# Nixie_Control_Board.net
KiCad netlist of a schematic drawn in EasyEDA
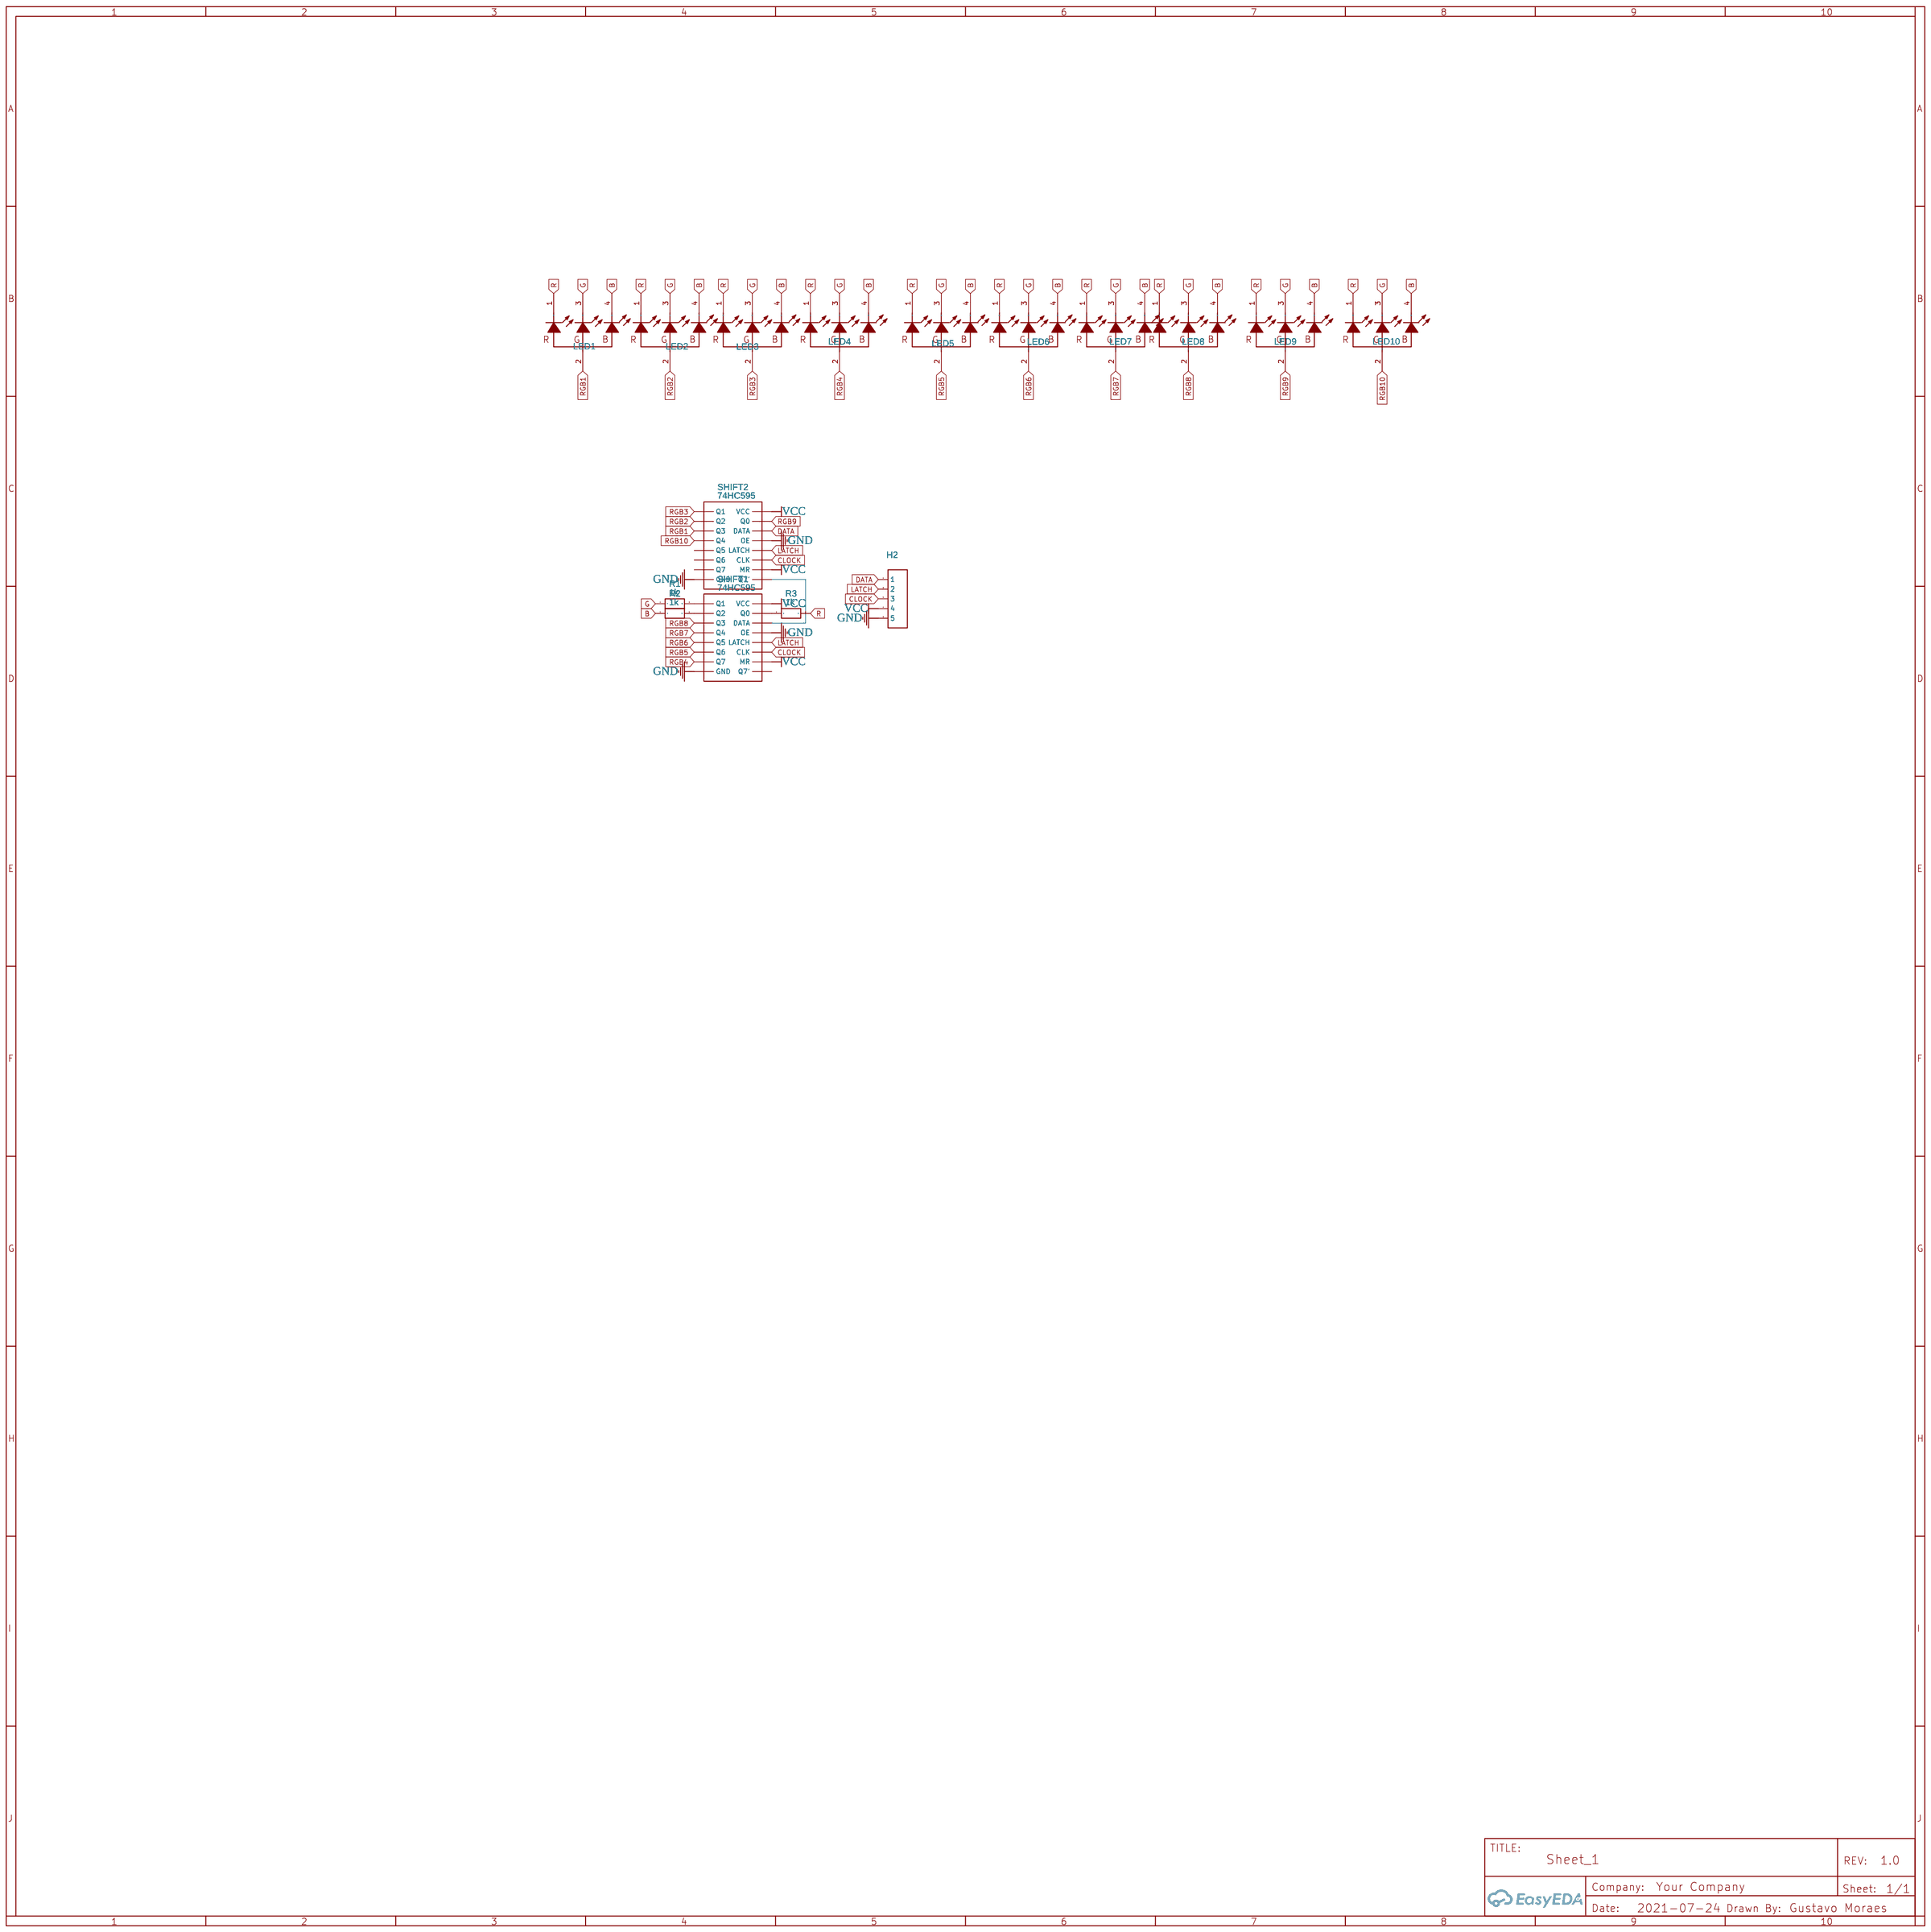
[diagram p0: schematic sheet]

(export (version "E")
  (design (tool "Eeschema 10.0.6"))
  (components
    (comp (ref "H2")
      (value "HDR-F-2.54_1x5")
      (fields (field (name "BOM_Supplier Part") "C50950"))
      (libsource (lib "") (part "HDR-F-2.54_1x5"))
    )
    (comp (ref "LED1")
      (value "φ5 RGB Transparent")
      (fields
        (field (name "BOM_Manufacturer Part") "φ5 RGB Transparent LED")
        (field (name "BOM_Supplier Part") "C32985")
      )
      (libsource (lib "") (part "φ5 RGB Transparent"))
    )
    (comp (ref "LED2")
      (value "φ5 RGB Transparent")
      (fields
        (field (name "BOM_Manufacturer Part") "φ5 RGB Transparent LED")
        (field (name "BOM_Supplier Part") "C32985")
      )
      (libsource (lib "") (part "φ5 RGB Transparent"))
    )
    (comp (ref "LED3")
      (value "φ5 RGB Transparent")
      (fields
        (field (name "BOM_Manufacturer Part") "φ5 RGB Transparent LED")
        (field (name "BOM_Supplier Part") "C32985")
      )
      (libsource (lib "") (part "φ5 RGB Transparent"))
    )
    (comp (ref "LED4")
      (value "φ5 RGB Transparent")
      (fields
        (field (name "BOM_Manufacturer Part") "φ5 RGB Transparent LED")
        (field (name "BOM_Supplier Part") "C32985")
      )
      (libsource (lib "") (part "φ5 RGB Transparent_1"))
    )
    (comp (ref "LED5")
      (value "φ5 RGB Transparent")
      (fields
        (field (name "BOM_Manufacturer Part") "φ5 RGB Transparent LED")
        (field (name "BOM_Supplier Part") "C32985")
      )
      (libsource (lib "") (part "φ5 RGB Transparent"))
    )
    (comp (ref "LED6")
      (value "φ5 RGB Transparent")
      (fields
        (field (name "BOM_Manufacturer Part") "φ5 RGB Transparent LED")
        (field (name "BOM_Supplier Part") "C32985")
      )
      (libsource (lib "") (part "φ5 RGB Transparent"))
    )
    (comp (ref "LED7")
      (value "φ5 RGB Transparent")
      (fields
        (field (name "BOM_Manufacturer Part") "φ5 RGB Transparent LED")
        (field (name "BOM_Supplier Part") "C32985")
      )
      (libsource (lib "") (part "φ5 RGB Transparent"))
    )
    (comp (ref "LED8")
      (value "φ5 RGB Transparent")
      (fields
        (field (name "BOM_Manufacturer Part") "φ5 RGB Transparent LED")
        (field (name "BOM_Supplier Part") "C32985")
      )
      (libsource (lib "") (part "φ5 RGB Transparent"))
    )
    (comp (ref "LED9")
      (value "φ5 RGB Transparent")
      (fields
        (field (name "BOM_Manufacturer Part") "φ5 RGB Transparent LED")
        (field (name "BOM_Supplier Part") "C32985")
      )
      (libsource (lib "") (part "φ5 RGB Transparent"))
    )
    (comp (ref "LED10")
      (value "φ5 RGB Transparent")
      (fields
        (field (name "BOM_Manufacturer Part") "φ5 RGB Transparent LED")
        (field (name "BOM_Supplier Part") "C32985")
      )
      (libsource (lib "") (part "φ5 RGB Transparent"))
    )
    (comp (ref "R1") (value "1k") (libsource (lib "") (part "R_AXIAL-0.3_EU")))
    (comp (ref "R2") (value "1k") (libsource (lib "") (part "R_AXIAL-0.3_EU")))
    (comp (ref "R3") (value "1k") (libsource (lib "") (part "R_AXIAL-0.3_EU")))
    (comp (ref "SHIFT1") (value "74HC595") (libsource (lib "") (part "74HC595")))
    (comp (ref "SHIFT2") (value "74HC595") (libsource (lib "") (part "74HC595")))
  )
  (nets
    (net (code "1") (name "B") (class "Default")
      (node (ref "LED1") (pin "4") (pinfunction "KB_4") (pintype "unspecified"))
      (node (ref "LED10") (pin "4") (pinfunction "KB_4") (pintype "unspecified"))
      (node (ref "LED2") (pin "4") (pinfunction "KB_4") (pintype "unspecified"))
      (node (ref "LED3") (pin "4") (pinfunction "KB_4") (pintype "unspecified"))
      (node (ref "LED4") (pin "4") (pinfunction "KB_4") (pintype "unspecified"))
      (node (ref "LED5") (pin "4") (pinfunction "KB_4") (pintype "unspecified"))
      (node (ref "LED6") (pin "4") (pinfunction "KB_4") (pintype "unspecified"))
      (node (ref "LED7") (pin "4") (pinfunction "KB_4") (pintype "unspecified"))
      (node (ref "LED8") (pin "4") (pinfunction "KB_4") (pintype "unspecified"))
      (node (ref "LED9") (pin "4") (pinfunction "KB_4") (pintype "unspecified"))
      (node (ref "R2") (pin "1") (pinfunction "1_1") (pintype "unspecified"))
    )
    (net (code "2") (name "CLOCK") (class "Default")
      (node (ref "H2") (pin "3") (pinfunction "3_3") (pintype "unspecified"))
      (node (ref "SHIFT1") (pin "11") (pinfunction "CLK_11") (pintype "unspecified"))
      (node (ref "SHIFT2") (pin "11") (pinfunction "CLK_11") (pintype "unspecified"))
    )
    (net (code "3") (name "DATA") (class "Default")
      (node (ref "H2") (pin "1") (pinfunction "1_1") (pintype "unspecified"))
      (node (ref "SHIFT2") (pin "14") (pinfunction "DATA_14") (pintype "unspecified"))
    )
    (net (code "4") (name "G") (class "Default")
      (node (ref "LED1") (pin "3") (pinfunction "KG_3") (pintype "unspecified"))
      (node (ref "LED10") (pin "3") (pinfunction "KG_3") (pintype "unspecified"))
      (node (ref "LED2") (pin "3") (pinfunction "KG_3") (pintype "unspecified"))
      (node (ref "LED3") (pin "3") (pinfunction "KG_3") (pintype "unspecified"))
      (node (ref "LED4") (pin "3") (pinfunction "KG_3") (pintype "unspecified"))
      (node (ref "LED5") (pin "3") (pinfunction "KG_3") (pintype "unspecified"))
      (node (ref "LED6") (pin "3") (pinfunction "KG_3") (pintype "unspecified"))
      (node (ref "LED7") (pin "3") (pinfunction "KG_3") (pintype "unspecified"))
      (node (ref "LED8") (pin "3") (pinfunction "KG_3") (pintype "unspecified"))
      (node (ref "LED9") (pin "3") (pinfunction "KG_3") (pintype "unspecified"))
      (node (ref "R1") (pin "1") (pinfunction "1_1") (pintype "unspecified"))
    )
    (net (code "5") (name "GND") (class "Default")
      (node (ref "H2") (pin "5") (pinfunction "5_5") (pintype "unspecified"))
      (node (ref "SHIFT1") (pin "13") (pinfunction "OE_13") (pintype "unspecified"))
      (node (ref "SHIFT1") (pin "8") (pinfunction "GND_8") (pintype "unspecified"))
      (node (ref "SHIFT2") (pin "13") (pinfunction "OE_13") (pintype "unspecified"))
      (node (ref "SHIFT2") (pin "8") (pinfunction "GND_8") (pintype "unspecified"))
    )
    (net (code "6") (name "LATCH") (class "Default")
      (node (ref "H2") (pin "2") (pinfunction "2_2") (pintype "unspecified"))
      (node (ref "SHIFT1") (pin "12") (pinfunction "LATCH_12") (pintype "unspecified"))
      (node (ref "SHIFT2") (pin "12") (pinfunction "LATCH_12") (pintype "unspecified"))
    )
    (net (code "7") (name "Net-(SHIFT1-DATA)") (class "Default")
      (node (ref "SHIFT1") (pin "14") (pinfunction "DATA_14") (pintype "unspecified"))
      (node (ref "SHIFT2") (pin "9") (pinfunction "Q7'_9") (pintype "unspecified"))
    )
    (net (code "8") (name "Net-(SHIFT1-Q0)") (class "Default")
      (node (ref "R3") (pin "1") (pinfunction "1_1") (pintype "unspecified"))
      (node (ref "SHIFT1") (pin "15") (pinfunction "Q0_15") (pintype "unspecified"))
    )
    (net (code "9") (name "Net-(SHIFT1-Q1)") (class "Default")
      (node (ref "R1") (pin "2") (pinfunction "2_2") (pintype "unspecified"))
      (node (ref "SHIFT1") (pin "1") (pinfunction "Q1_1") (pintype "unspecified"))
    )
    (net (code "10") (name "Net-(SHIFT1-Q2)") (class "Default")
      (node (ref "R2") (pin "2") (pinfunction "2_2") (pintype "unspecified"))
      (node (ref "SHIFT1") (pin "2") (pinfunction "Q2_2") (pintype "unspecified"))
    )
    (net (code "11") (name "R") (class "Default")
      (node (ref "LED1") (pin "1") (pinfunction "KR_1") (pintype "unspecified"))
      (node (ref "LED10") (pin "1") (pinfunction "KR_1") (pintype "unspecified"))
      (node (ref "LED2") (pin "1") (pinfunction "KR_1") (pintype "unspecified"))
      (node (ref "LED3") (pin "1") (pinfunction "KR_1") (pintype "unspecified"))
      (node (ref "LED4") (pin "1") (pinfunction "KR_1") (pintype "unspecified"))
      (node (ref "LED5") (pin "1") (pinfunction "KR_1") (pintype "unspecified"))
      (node (ref "LED6") (pin "1") (pinfunction "KR_1") (pintype "unspecified"))
      (node (ref "LED7") (pin "1") (pinfunction "KR_1") (pintype "unspecified"))
      (node (ref "LED8") (pin "1") (pinfunction "KR_1") (pintype "unspecified"))
      (node (ref "LED9") (pin "1") (pinfunction "KR_1") (pintype "unspecified"))
      (node (ref "R3") (pin "2") (pinfunction "2_2") (pintype "unspecified"))
    )
    (net (code "12") (name "RGB1") (class "Default")
      (node (ref "LED1") (pin "2") (pinfunction "CA_2") (pintype "unspecified"))
      (node (ref "SHIFT2") (pin "3") (pinfunction "Q3_3") (pintype "unspecified"))
    )
    (net (code "13") (name "RGB2") (class "Default")
      (node (ref "LED2") (pin "2") (pinfunction "CA_2") (pintype "unspecified"))
      (node (ref "SHIFT2") (pin "2") (pinfunction "Q2_2") (pintype "unspecified"))
    )
    (net (code "14") (name "RGB3") (class "Default")
      (node (ref "LED3") (pin "2") (pinfunction "CA_2") (pintype "unspecified"))
      (node (ref "SHIFT2") (pin "1") (pinfunction "Q1_1") (pintype "unspecified"))
    )
    (net (code "15") (name "RGB4") (class "Default")
      (node (ref "LED4") (pin "2") (pinfunction "CA_2") (pintype "unspecified"))
      (node (ref "SHIFT1") (pin "7") (pinfunction "Q7_7") (pintype "unspecified"))
    )
    (net (code "16") (name "RGB5") (class "Default")
      (node (ref "LED5") (pin "2") (pinfunction "CA_2") (pintype "unspecified"))
      (node (ref "SHIFT1") (pin "6") (pinfunction "Q6_6") (pintype "unspecified"))
    )
    (net (code "17") (name "RGB6") (class "Default")
      (node (ref "LED6") (pin "2") (pinfunction "CA_2") (pintype "unspecified"))
      (node (ref "SHIFT1") (pin "5") (pinfunction "Q5_5") (pintype "unspecified"))
    )
    (net (code "18") (name "RGB7") (class "Default")
      (node (ref "LED7") (pin "2") (pinfunction "CA_2") (pintype "unspecified"))
      (node (ref "SHIFT1") (pin "4") (pinfunction "Q4_4") (pintype "unspecified"))
    )
    (net (code "19") (name "RGB8") (class "Default")
      (node (ref "LED8") (pin "2") (pinfunction "CA_2") (pintype "unspecified"))
      (node (ref "SHIFT1") (pin "3") (pinfunction "Q3_3") (pintype "unspecified"))
    )
    (net (code "20") (name "RGB9") (class "Default")
      (node (ref "LED9") (pin "2") (pinfunction "CA_2") (pintype "unspecified"))
      (node (ref "SHIFT2") (pin "15") (pinfunction "Q0_15") (pintype "unspecified"))
    )
    (net (code "21") (name "RGB10") (class "Default")
      (node (ref "LED10") (pin "2") (pinfunction "CA_2") (pintype "unspecified"))
      (node (ref "SHIFT2") (pin "4") (pinfunction "Q4_4") (pintype "unspecified"))
    )
    (net (code "22") (name "VCC") (class "Default")
      (node (ref "H2") (pin "4") (pinfunction "4_4") (pintype "unspecified"))
      (node (ref "SHIFT1") (pin "10") (pinfunction "MR_10") (pintype "unspecified"))
      (node (ref "SHIFT1") (pin "16") (pinfunction "VCC_16") (pintype "unspecified"))
      (node (ref "SHIFT2") (pin "10") (pinfunction "MR_10") (pintype "unspecified"))
      (node (ref "SHIFT2") (pin "16") (pinfunction "VCC_16") (pintype "unspecified"))
    )
    (net (code "23") (name "unconnected-(SHIFT1-Q7'-Pad9)") (class "Default")
      (node (ref "SHIFT1") (pin "9") (pinfunction "Q7'_9") (pintype "unspecified"))
    )
    (net (code "24") (name "unconnected-(SHIFT2-Q5-Pad5)") (class "Default")
      (node (ref "SHIFT2") (pin "5") (pinfunction "Q5_5") (pintype "unspecified"))
    )
    (net (code "25") (name "unconnected-(SHIFT2-Q6-Pad6)") (class "Default")
      (node (ref "SHIFT2") (pin "6") (pinfunction "Q6_6") (pintype "unspecified"))
    )
    (net (code "26") (name "unconnected-(SHIFT2-Q7-Pad7)") (class "Default")
      (node (ref "SHIFT2") (pin "7") (pinfunction "Q7_7") (pintype "unspecified"))
    )
  )
)
